# Robot.net
KiCad netlist of a schematic drawn in EAGLE
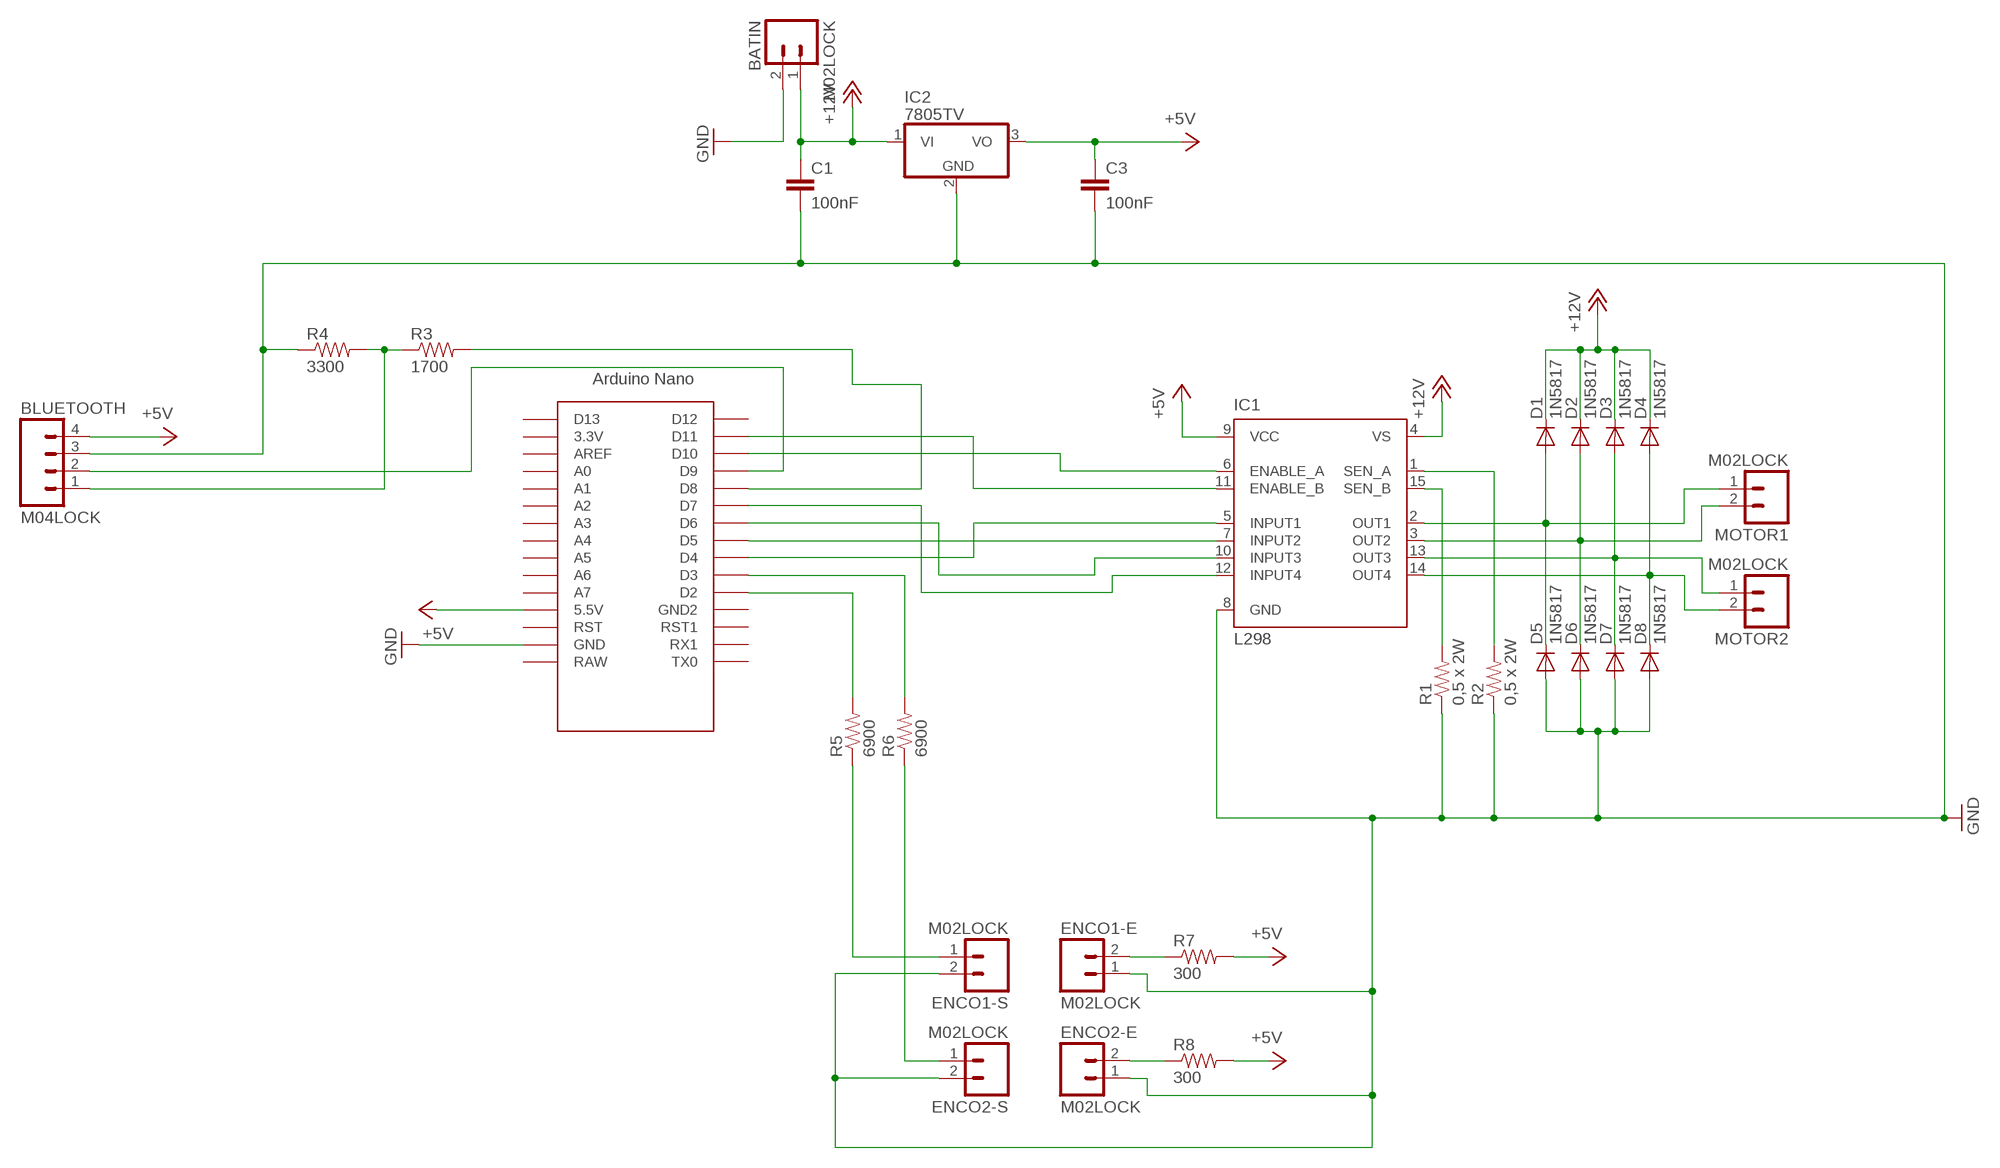
[diagram p0: schematic, sheet 1]

(export (version "E")
  (design (tool "Eeschema 10.0.6"))
  (components
    (comp (ref "BATIN")
      (value "M02LOCK")
      (footprint "eagle-import:1X02_LOCK")
      (libsource (lib "eagle-import") (part "M02LOCK"))
    )
    (comp (ref "BLUETOOTH")
      (value "M04LOCK")
      (footprint "eagle-import:1X04_LOCK")
      (libsource (lib "eagle-import") (part "M04LOCK"))
    )
    (comp (ref "C1")
      (value "100nF")
      (footprint "eagle-import:C050-025X075")
      (libsource (lib "eagle-import") (part "C-EU050-025X075"))
    )
    (comp (ref "C3")
      (value "100nF")
      (footprint "eagle-import:C050-025X075")
      (libsource (lib "eagle-import") (part "C-EU050-025X075"))
    )
    (comp (ref "D1")
      (value "1N5817")
      (footprint "eagle-import:DO41-10")
      (libsource (lib "eagle-import") (part "1N4004"))
    )
    (comp (ref "D2")
      (value "1N5817")
      (footprint "eagle-import:DO41-10")
      (libsource (lib "eagle-import") (part "1N4004"))
    )
    (comp (ref "D3")
      (value "1N5817")
      (footprint "eagle-import:DO41-10")
      (libsource (lib "eagle-import") (part "1N4004"))
    )
    (comp (ref "D4")
      (value "1N5817")
      (footprint "eagle-import:DO41-10")
      (libsource (lib "eagle-import") (part "1N4004"))
    )
    (comp (ref "D5")
      (value "1N5817")
      (footprint "eagle-import:DO41-10")
      (libsource (lib "eagle-import") (part "1N4004"))
    )
    (comp (ref "D6")
      (value "1N5817")
      (footprint "eagle-import:DO41-10")
      (libsource (lib "eagle-import") (part "1N4004"))
    )
    (comp (ref "D7")
      (value "1N5817")
      (footprint "eagle-import:DO41-10")
      (libsource (lib "eagle-import") (part "1N4004"))
    )
    (comp (ref "D8")
      (value "1N5817")
      (footprint "eagle-import:DO41-10")
      (libsource (lib "eagle-import") (part "1N4004"))
    )
    (comp (ref "ENCO1-E")
      (value "M02LOCK")
      (footprint "eagle-import:1X02_LOCK")
      (libsource (lib "eagle-import") (part "M02LOCK"))
    )
    (comp (ref "ENCO1-S")
      (value "M02LOCK")
      (footprint "eagle-import:1X02_LOCK")
      (libsource (lib "eagle-import") (part "M02LOCK"))
    )
    (comp (ref "ENCO2-E")
      (value "M02LOCK")
      (footprint "eagle-import:1X02_LOCK")
      (libsource (lib "eagle-import") (part "M02LOCK"))
    )
    (comp (ref "ENCO2-S")
      (value "M02LOCK")
      (footprint "eagle-import:1X02_LOCK")
      (libsource (lib "eagle-import") (part "M02LOCK"))
    )
    (comp (ref "IC1")
      (value "L298")
      (footprint "eagle-import:MULTIWATT-15")
      (libsource (lib "eagle-import") (part "L298"))
    )
    (comp (ref "IC2")
      (value "7805TV")
      (footprint "eagle-import:TO220V")
      (libsource (lib "eagle-import") (part "78TV05"))
    )
    (comp (ref "MOTOR1")
      (value "M02LOCK")
      (footprint "eagle-import:1X02_LOCK")
      (libsource (lib "eagle-import") (part "M02LOCK"))
    )
    (comp (ref "MOTOR2")
      (value "M02LOCK")
      (footprint "eagle-import:1X02_LOCK")
      (libsource (lib "eagle-import") (part "M02LOCK"))
    )
    (comp (ref "R1")
      (value "0,5 x 2W")
      (footprint "eagle-import:AXIAL-0.5")
      (libsource (lib "eagle-import") (part "RESISTORPTH-1/2W"))
    )
    (comp (ref "R2")
      (value "0,5 x 2W")
      (footprint "eagle-import:AXIAL-0.5")
      (libsource (lib "eagle-import") (part "RESISTORPTH-1/2W"))
    )
    (comp (ref "R3")
      (value "1700")
      (footprint "eagle-import:AXIAL-0.3")
      (libsource (lib "eagle-import") (part "RESISTORAXIAL-0.3"))
    )
    (comp (ref "R4")
      (value "3300")
      (footprint "eagle-import:AXIAL-0.3")
      (libsource (lib "eagle-import") (part "RESISTORAXIAL-0.3"))
    )
    (comp (ref "R5")
      (value "6900")
      (footprint "eagle-import:AXIAL-0.3")
      (libsource (lib "eagle-import") (part "RESISTORAXIAL-0.3"))
    )
    (comp (ref "R6")
      (value "6900")
      (footprint "eagle-import:AXIAL-0.3")
      (libsource (lib "eagle-import") (part "RESISTORAXIAL-0.3"))
    )
    (comp (ref "R7")
      (value "300")
      (footprint "eagle-import:AXIAL-0.3")
      (libsource (lib "eagle-import") (part "RESISTORAXIAL-0.3"))
    )
    (comp (ref "R8")
      (value "300")
      (footprint "eagle-import:AXIAL-0.3")
      (libsource (lib "eagle-import") (part "RESISTORAXIAL-0.3"))
    )
    (comp (ref "U$1")
      (value "NANO")
      (footprint "eagle-import:NANO")
      (libsource (lib "eagle-import") (part "NANO"))
    )
  )
  (nets
    (net (code "1") (name "+5V") (class "Default")
      (node (ref "BLUETOOTH") (pin "4") (pinfunction "4_4") (pintype "passive"))
      (node (ref "C3") (pin "1") (pinfunction "1_1") (pintype "passive"))
      (node (ref "IC1") (pin "9") (pinfunction "VCC_9") (pintype "power_in"))
      (node (ref "IC2") (pin "3") (pinfunction "VO_3") (pintype "passive"))
      (node (ref "R7") (pin "P$2") (pinfunction "2_P$2") (pintype "passive"))
      (node (ref "R8") (pin "P$2") (pinfunction "2_P$2") (pintype "passive"))
      (node (ref "U$1") (pin "5V") (pinfunction "5.5V_5V") (pintype "bidirectional"))
    )
    (net (code "2") (name "+12V") (class "Default")
      (node (ref "BATIN") (pin "1") (pinfunction "1_1") (pintype "passive"))
      (node (ref "C1") (pin "1") (pinfunction "1_1") (pintype "passive"))
      (node (ref "D1") (pin "C") (pinfunction "C_C") (pintype "passive"))
      (node (ref "D2") (pin "C") (pinfunction "C_C") (pintype "passive"))
      (node (ref "D3") (pin "C") (pinfunction "C_C") (pintype "passive"))
      (node (ref "D4") (pin "C") (pinfunction "C_C") (pintype "passive"))
      (node (ref "IC1") (pin "4") (pinfunction "VS_4") (pintype "power_in"))
      (node (ref "IC2") (pin "1") (pinfunction "VI_1") (pintype "input"))
    )
    (net (code "3") (name "GND") (class "Default")
      (node (ref "BATIN") (pin "2") (pinfunction "2_2") (pintype "passive"))
      (node (ref "BLUETOOTH") (pin "3") (pinfunction "3_3") (pintype "passive"))
      (node (ref "C1") (pin "2") (pinfunction "2_2") (pintype "passive"))
      (node (ref "C3") (pin "2") (pinfunction "2_2") (pintype "passive"))
      (node (ref "D5") (pin "A") (pinfunction "A_A") (pintype "passive"))
      (node (ref "D6") (pin "A") (pinfunction "A_A") (pintype "passive"))
      (node (ref "D7") (pin "A") (pinfunction "A_A") (pintype "passive"))
      (node (ref "D8") (pin "A") (pinfunction "A_A") (pintype "passive"))
      (node (ref "ENCO1-E") (pin "1") (pinfunction "1_1") (pintype "passive"))
      (node (ref "ENCO1-S") (pin "2") (pinfunction "2_2") (pintype "passive"))
      (node (ref "ENCO2-E") (pin "1") (pinfunction "1_1") (pintype "passive"))
      (node (ref "ENCO2-S") (pin "2") (pinfunction "2_2") (pintype "passive"))
      (node (ref "IC1") (pin "8") (pinfunction "GND_8") (pintype "power_in"))
      (node (ref "IC2") (pin "2") (pinfunction "GND_2") (pintype "passive"))
      (node (ref "R1") (pin "P$1") (pinfunction "1_P$1") (pintype "passive"))
      (node (ref "R2") (pin "P$1") (pinfunction "1_P$1") (pintype "passive"))
      (node (ref "R4") (pin "P$1") (pinfunction "1_P$1") (pintype "passive"))
      (node (ref "U$1") (pin "GND") (pinfunction "GND_GND") (pintype "bidirectional"))
    )
    (net (code "4") (name "Net-(BLUETOOTH-Pad2)") (class "Default")
      (node (ref "BLUETOOTH") (pin "2") (pinfunction "2_2") (pintype "passive"))
      (node (ref "U$1") (pin "D9") (pinfunction "D9_D9") (pintype "bidirectional"))
    )
    (net (code "5") (name "Net-(IC1-ENABLE_A)") (class "Default")
      (node (ref "IC1") (pin "6") (pinfunction "ENABLE_A_6") (pintype "input"))
      (node (ref "U$1") (pin "D10") (pinfunction "D10_D10") (pintype "bidirectional"))
    )
    (net (code "6") (name "Net-(IC1-ENABLE_B)") (class "Default")
      (node (ref "IC1") (pin "11") (pinfunction "ENABLE_B_11") (pintype "input"))
      (node (ref "U$1") (pin "D11") (pinfunction "D11_D11") (pintype "bidirectional"))
    )
    (net (code "7") (name "Net-(IC1-INPUT1)") (class "Default")
      (node (ref "IC1") (pin "5") (pinfunction "INPUT1_5") (pintype "input"))
      (node (ref "U$1") (pin "D4") (pinfunction "D4_D4") (pintype "bidirectional"))
    )
    (net (code "8") (name "Net-(IC1-INPUT2)") (class "Default")
      (node (ref "IC1") (pin "7") (pinfunction "INPUT2_7") (pintype "input"))
      (node (ref "U$1") (pin "D5") (pinfunction "D5_D5") (pintype "bidirectional"))
    )
    (net (code "9") (name "Net-(IC1-INPUT3)") (class "Default")
      (node (ref "IC1") (pin "10") (pinfunction "INPUT3_10") (pintype "input"))
      (node (ref "U$1") (pin "D6") (pinfunction "D6_D6") (pintype "bidirectional"))
    )
    (net (code "10") (name "Net-(IC1-INPUT4)") (class "Default")
      (node (ref "IC1") (pin "12") (pinfunction "INPUT4_12") (pintype "input"))
      (node (ref "U$1") (pin "D7") (pinfunction "D7_D7") (pintype "bidirectional"))
    )
    (net (code "11") (name "Net-(IC1-OUT1)") (class "Default")
      (node (ref "D1") (pin "A") (pinfunction "A_A") (pintype "passive"))
      (node (ref "D5") (pin "C") (pinfunction "C_C") (pintype "passive"))
      (node (ref "IC1") (pin "2") (pinfunction "OUT1_2") (pintype "output"))
      (node (ref "MOTOR1") (pin "1") (pinfunction "1_1") (pintype "passive"))
    )
    (net (code "12") (name "Net-(IC1-OUT2)") (class "Default")
      (node (ref "D2") (pin "A") (pinfunction "A_A") (pintype "passive"))
      (node (ref "D6") (pin "C") (pinfunction "C_C") (pintype "passive"))
      (node (ref "IC1") (pin "3") (pinfunction "OUT2_3") (pintype "output"))
      (node (ref "MOTOR1") (pin "2") (pinfunction "2_2") (pintype "passive"))
    )
    (net (code "13") (name "Net-(IC1-OUT3)") (class "Default")
      (node (ref "D3") (pin "A") (pinfunction "A_A") (pintype "passive"))
      (node (ref "D7") (pin "C") (pinfunction "C_C") (pintype "passive"))
      (node (ref "IC1") (pin "13") (pinfunction "OUT3_13") (pintype "output"))
      (node (ref "MOTOR2") (pin "1") (pinfunction "1_1") (pintype "passive"))
    )
    (net (code "14") (name "Net-(IC1-OUT4)") (class "Default")
      (node (ref "D4") (pin "A") (pinfunction "A_A") (pintype "passive"))
      (node (ref "D8") (pin "C") (pinfunction "C_C") (pintype "passive"))
      (node (ref "IC1") (pin "14") (pinfunction "OUT4_14") (pintype "output"))
      (node (ref "MOTOR2") (pin "2") (pinfunction "2_2") (pintype "passive"))
    )
    (net (code "15") (name "Net-(IC1-SEN_A)") (class "Default")
      (node (ref "IC1") (pin "1") (pinfunction "SEN_A_1") (pintype "input"))
      (node (ref "R2") (pin "P$2") (pinfunction "2_P$2") (pintype "passive"))
    )
    (net (code "16") (name "Net-(IC1-SEN_B)") (class "Default")
      (node (ref "IC1") (pin "15") (pinfunction "SEN_B_15") (pintype "input"))
      (node (ref "R1") (pin "P$2") (pinfunction "2_P$2") (pintype "passive"))
    )
    (net (code "17") (name "Net-(R3-1)") (class "Default")
      (node (ref "BLUETOOTH") (pin "1") (pinfunction "1_1") (pintype "passive"))
      (node (ref "R3") (pin "P$1") (pinfunction "1_P$1") (pintype "passive"))
      (node (ref "R4") (pin "P$2") (pinfunction "2_P$2") (pintype "passive"))
    )
    (net (code "18") (name "Net-(R3-2)") (class "Default")
      (node (ref "R3") (pin "P$2") (pinfunction "2_P$2") (pintype "passive"))
      (node (ref "U$1") (pin "D8") (pinfunction "D8_D8") (pintype "bidirectional"))
    )
    (net (code "19") (name "Net-(R5-1)") (class "Default")
      (node (ref "ENCO1-S") (pin "1") (pinfunction "1_1") (pintype "passive"))
      (node (ref "R5") (pin "P$1") (pinfunction "1_P$1") (pintype "passive"))
    )
    (net (code "20") (name "Net-(R5-2)") (class "Default")
      (node (ref "R5") (pin "P$2") (pinfunction "2_P$2") (pintype "passive"))
      (node (ref "U$1") (pin "D2") (pinfunction "D2_D2") (pintype "bidirectional"))
    )
    (net (code "21") (name "Net-(R6-1)") (class "Default")
      (node (ref "ENCO2-S") (pin "1") (pinfunction "1_1") (pintype "passive"))
      (node (ref "R6") (pin "P$1") (pinfunction "1_P$1") (pintype "passive"))
    )
    (net (code "22") (name "Net-(R6-2)") (class "Default")
      (node (ref "R6") (pin "P$2") (pinfunction "2_P$2") (pintype "passive"))
      (node (ref "U$1") (pin "D3") (pinfunction "D3_D3") (pintype "bidirectional"))
    )
    (net (code "23") (name "Net-(R7-1)") (class "Default")
      (node (ref "ENCO1-E") (pin "2") (pinfunction "2_2") (pintype "passive"))
      (node (ref "R7") (pin "P$1") (pinfunction "1_P$1") (pintype "passive"))
    )
    (net (code "24") (name "Net-(R8-1)") (class "Default")
      (node (ref "ENCO2-E") (pin "2") (pinfunction "2_2") (pintype "passive"))
      (node (ref "R8") (pin "P$1") (pinfunction "1_P$1") (pintype "passive"))
    )
    (net (code "25") (name "unconnected-(U$1-GND2-PadGND1)") (class "Default")
      (node (ref "U$1") (pin "GND1") (pinfunction "GND2_GND1") (pintype "bidirectional"))
    )
    (net (code "26") (name "unconnected-(U$1-Pad3.3V)") (class "Default")
      (node (ref "U$1") (pin "3.3V") (pinfunction "3.3V_3.3V") (pintype "bidirectional"))
    )
    (net (code "27") (name "unconnected-(U$1-PadA0)") (class "Default")
      (node (ref "U$1") (pin "A0") (pinfunction "A0_A0") (pintype "bidirectional"))
    )
    (net (code "28") (name "unconnected-(U$1-PadA1)") (class "Default")
      (node (ref "U$1") (pin "A1") (pinfunction "A1_A1") (pintype "bidirectional"))
    )
    (net (code "29") (name "unconnected-(U$1-PadA2)") (class "Default")
      (node (ref "U$1") (pin "A2") (pinfunction "A2_A2") (pintype "bidirectional"))
    )
    (net (code "30") (name "unconnected-(U$1-PadA3)") (class "Default")
      (node (ref "U$1") (pin "A3") (pinfunction "A3_A3") (pintype "bidirectional"))
    )
    (net (code "31") (name "unconnected-(U$1-PadA4)") (class "Default")
      (node (ref "U$1") (pin "A4") (pinfunction "A4_A4") (pintype "bidirectional"))
    )
    (net (code "32") (name "unconnected-(U$1-PadA5)") (class "Default")
      (node (ref "U$1") (pin "A5") (pinfunction "A5_A5") (pintype "bidirectional"))
    )
    (net (code "33") (name "unconnected-(U$1-PadA6)") (class "Default")
      (node (ref "U$1") (pin "A6") (pinfunction "A6_A6") (pintype "bidirectional"))
    )
    (net (code "34") (name "unconnected-(U$1-PadA7)") (class "Default")
      (node (ref "U$1") (pin "A7") (pinfunction "A7_A7") (pintype "bidirectional"))
    )
    (net (code "35") (name "unconnected-(U$1-PadAREF)") (class "Default")
      (node (ref "U$1") (pin "AREF") (pinfunction "AREF_AREF") (pintype "bidirectional"))
    )
    (net (code "36") (name "unconnected-(U$1-PadD12)") (class "Default")
      (node (ref "U$1") (pin "D12") (pinfunction "D12_D12") (pintype "bidirectional"))
    )
    (net (code "37") (name "unconnected-(U$1-PadD13)") (class "Default")
      (node (ref "U$1") (pin "D13") (pinfunction "D13_D13") (pintype "bidirectional"))
    )
    (net (code "38") (name "unconnected-(U$1-PadICSP1)") (class "Default")
      (node (ref "U$1") (pin "ICSP1") (pinfunction "ICSP1_ICSP1") (pintype "bidirectional"))
    )
    (net (code "39") (name "unconnected-(U$1-PadICSP2)") (class "Default")
      (node (ref "U$1") (pin "ICSP2") (pinfunction "ICSP2_ICSP2") (pintype "bidirectional"))
    )
    (net (code "40") (name "unconnected-(U$1-PadICSP3)") (class "Default")
      (node (ref "U$1") (pin "ICSP3") (pinfunction "ICSP3_ICSP3") (pintype "bidirectional"))
    )
    (net (code "41") (name "unconnected-(U$1-PadICSP4)") (class "Default")
      (node (ref "U$1") (pin "ICSP4") (pinfunction "ICSP4_ICSP4") (pintype "bidirectional"))
    )
    (net (code "42") (name "unconnected-(U$1-PadICSP5)") (class "Default")
      (node (ref "U$1") (pin "ICSP5") (pinfunction "ICSP5_ICSP5") (pintype "bidirectional"))
    )
    (net (code "43") (name "unconnected-(U$1-PadICSP6)") (class "Default")
      (node (ref "U$1") (pin "ICSP6") (pinfunction "ICSP6_ICSP6") (pintype "bidirectional"))
    )
    (net (code "44") (name "unconnected-(U$1-PadRAW)") (class "Default")
      (node (ref "U$1") (pin "RAW") (pinfunction "RAW_RAW") (pintype "bidirectional"))
    )
    (net (code "45") (name "unconnected-(U$1-PadRST)") (class "Default")
      (node (ref "U$1") (pin "RST") (pinfunction "RST_RST") (pintype "bidirectional"))
    )
    (net (code "46") (name "unconnected-(U$1-PadRST1)") (class "Default")
      (node (ref "U$1") (pin "RST1") (pinfunction "RST1_RST1") (pintype "bidirectional"))
    )
    (net (code "47") (name "unconnected-(U$1-PadRX1)") (class "Default")
      (node (ref "U$1") (pin "RX1") (pinfunction "RX1_RX1") (pintype "bidirectional"))
    )
    (net (code "48") (name "unconnected-(U$1-PadTX0)") (class "Default")
      (node (ref "U$1") (pin "TX0") (pinfunction "TX0_TX0") (pintype "bidirectional"))
    )
  )
)
